# 2_MCU.net
KiCad netlist of a schematic drawn in Altium Designer
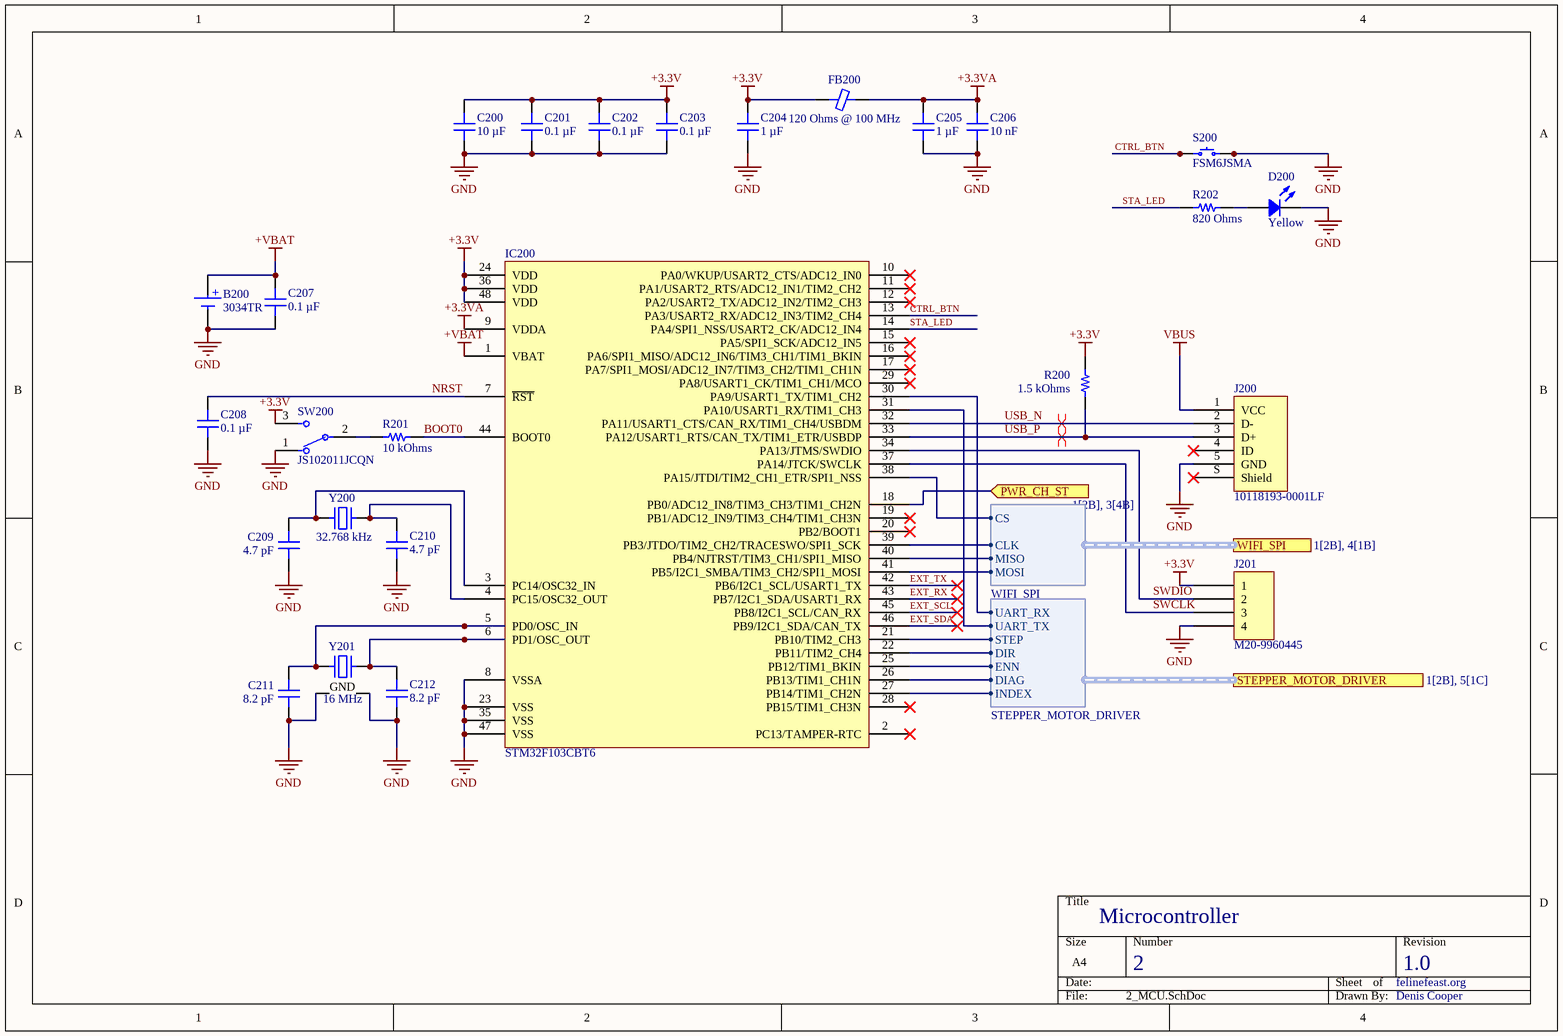
[diagram p0: 2_MCU.SchDoc]

(export (version "E")
  (design (tool "Eeschema 10.0.6"))
  (components
    (comp (ref "B200")
      (value "3034TR")
      (footprint "KEYSTONE 3034TR")
      (description "BATTERY RETAINER COIN 20MM SMD")
      (fields (field (name "MANUFACTURER") "Keystone Electronics"))
      (libsource (lib "Celestial Altium Library - altium_library") (part "KEYSTONE 3034TR"))
    )
    (comp (ref "C200")
      (value "10 µF")
      (footprint "CAP 0805_2012")
      (description "CAP CER 10UF 10V X7R 0805")
      (fields
        (field (name "PART NUMBER") "CL21B106KPQNNNE")
        (field (name "CAPACITANCE") "10 µF")
        (field (name "MANUFACTURER") "Samsung Electro-Mechanics")
      )
      (libsource (lib "Celestial Altium Library - altium_library") (part "Capacitor"))
    )
    (comp (ref "C201")
      (value "0.1 µF")
      (footprint "CAP 0603_1608")
      (description "CAP CER 0.1UF 25V X7R 0603")
      (fields
        (field (name "PART NUMBER") "CL10B104KA8NNNC")
        (field (name "CAPACITANCE") "0.1 µF")
        (field (name "MANUFACTURER") "Samsung Electro-Mechanics")
      )
      (libsource (lib "Celestial Altium Library - altium_library") (part "Capacitor"))
    )
    (comp (ref "C202")
      (value "0.1 µF")
      (footprint "CAP 0603_1608")
      (description "CAP CER 0.1UF 25V X7R 0603")
      (fields
        (field (name "PART NUMBER") "CL10B104KA8NNNC")
        (field (name "CAPACITANCE") "0.1 µF")
        (field (name "MANUFACTURER") "Samsung Electro-Mechanics")
      )
      (libsource (lib "Celestial Altium Library - altium_library") (part "Capacitor"))
    )
    (comp (ref "C203")
      (value "0.1 µF")
      (footprint "CAP 0603_1608")
      (description "CAP CER 0.1UF 25V X7R 0603")
      (fields
        (field (name "PART NUMBER") "CL10B104KA8NNNC")
        (field (name "CAPACITANCE") "0.1 µF")
        (field (name "MANUFACTURER") "Samsung Electro-Mechanics")
      )
      (libsource (lib "Celestial Altium Library - altium_library") (part "Capacitor"))
    )
    (comp (ref "C204")
      (value "1 µF")
      (footprint "CAP 0805_2012")
      (description "CAP CER 1UF 25V X7R 0805")
      (fields
        (field (name "PART NUMBER") "CL21B105KAFNFNE")
        (field (name "CAPACITANCE") "1 µF")
        (field (name "MANUFACTURER") "Samsung Electro-Mechanics")
      )
      (libsource (lib "Celestial Altium Library - altium_library") (part "Capacitor"))
    )
    (comp (ref "C205")
      (value "1 µF")
      (footprint "CAP 0805_2012")
      (description "CAP CER 1UF 25V X7R 0805")
      (fields
        (field (name "PART NUMBER") "CL21B105KAFNFNE")
        (field (name "CAPACITANCE") "1 µF")
        (field (name "MANUFACTURER") "Samsung Electro-Mechanics")
      )
      (libsource (lib "Celestial Altium Library - altium_library") (part "Capacitor"))
    )
    (comp (ref "C206")
      (value "10000 pF")
      (footprint "CAP 0603_1608")
      (description "CAP CER 10000PF 50V X7R 0603")
      (fields
        (field (name "PART NUMBER") "CL10B103KB8NNNC")
        (field (name "CAPACITANCE") "10 nF")
        (field (name "MANUFACTURER") "Samsung Electro-Mechanics")
      )
      (libsource (lib "Celestial Altium Library - altium_library") (part "Capacitor"))
    )
    (comp (ref "C207")
      (value "0.1 µF")
      (footprint "CAP 0603_1608")
      (description "CAP CER 0.1UF 25V X7R 0603")
      (fields
        (field (name "PART NUMBER") "CL10B104KA8NNNC")
        (field (name "CAPACITANCE") "0.1 µF")
        (field (name "MANUFACTURER") "Samsung Electro-Mechanics")
      )
      (libsource (lib "Celestial Altium Library - altium_library") (part "Capacitor"))
    )
    (comp (ref "C208")
      (value "0.1 µF")
      (footprint "CAP 0603_1608")
      (description "CAP CER 0.1UF 25V X7R 0603")
      (fields
        (field (name "PART NUMBER") "CL10B104KA8NNNC")
        (field (name "CAPACITANCE") "0.1 µF")
        (field (name "MANUFACTURER") "Samsung Electro-Mechanics")
      )
      (libsource (lib "Celestial Altium Library - altium_library") (part "Capacitor"))
    )
    (comp (ref "C209")
      (value "4.7 pF")
      (footprint "MURATA GJM155 0402_1005")
      (description "CAP CER 4.7PF 50V C0G/NP0 0402")
      (fields
        (field (name "PART NUMBER") "GJM1555C1H4R7GB01D")
        (field (name "CAPACITANCE") "4.7 pF")
        (field (name "MANUFACTURER") "Murata Electronics")
      )
      (libsource (lib "Celestial Altium Library - altium_library") (part "Capacitor"))
    )
    (comp (ref "C210")
      (value "4.7 pF")
      (footprint "MURATA GJM155 0402_1005")
      (description "CAP CER 4.7PF 50V C0G/NP0 0402")
      (fields
        (field (name "PART NUMBER") "GJM1555C1H4R7GB01D")
        (field (name "CAPACITANCE") "4.7 pF")
        (field (name "MANUFACTURER") "Murata Electronics")
      )
      (libsource (lib "Celestial Altium Library - altium_library") (part "Capacitor"))
    )
    (comp (ref "C211")
      (value "8.2 pF")
      (footprint "CAP 0603_1608")
      (description "CAP CER 8.2PF 50V C0G/NPO 0603")
      (fields
        (field (name "PART NUMBER") "CC0603JRNPO9BN8R2")
        (field (name "CAPACITANCE") "8.2 pF")
        (field (name "MANUFACTURER") "Yageo")
      )
      (libsource (lib "Celestial Altium Library - altium_library") (part "Capacitor"))
    )
    (comp (ref "C212")
      (value "8.2 pF")
      (footprint "CAP 0603_1608")
      (description "CAP CER 8.2PF 50V C0G/NPO 0603")
      (fields
        (field (name "PART NUMBER") "CC0603JRNPO9BN8R2")
        (field (name "CAPACITANCE") "8.2 pF")
        (field (name "MANUFACTURER") "Yageo")
      )
      (libsource (lib "Celestial Altium Library - altium_library") (part "Capacitor"))
    )
    (comp (ref "D200")
      (value "Yellow")
      (footprint "LED 0603_1608 YELLOW")
      (description "LED YELLOW DIFFUSED 0603 SMD")
      (fields
        (field (name "PART NUMBER") "LY L29K-H1K2-26-Z")
        (field (name "MANUFACTURER") "OSRAM Opto Semiconductors Inc.")
      )
      (libsource (lib "Celestial Altium Library - altium_library") (part "LED"))
    )
    (comp (ref "FB200")
      (value "120 Ohms @ 100 MHz")
      (footprint "FER 0603_1608")
      (description "FERRITE BEAD 120 OHM 0603 1LN")
      (fields
        (field (name "PART NUMBER") "GZ1608D121TF")
        (field (name "MANUFACTURER") "Shenzhen Sunlord Electronics Co., Ltd.")
      )
      (libsource (lib "Celestial Altium Library - altium_library") (part "Ferrite Chip"))
    )
    (comp (ref "IC200")
      (value "STM32F103CBT6")
      (footprint "ST LQFP-48 7X7MM")
      (description "IC MCU 32BIT 128KB FLASH 48LQFP")
      (fields (field (name "MANUFACTURER") "STMicroelectronics"))
      (libsource (lib "Celestial Altium Library - altium_library") (part "ST STM32F103 48PIN"))
    )
    (comp (ref "J200")
      (value "10118193-0001LF")
      (footprint "FCI USB 10118193-0001LF")
      (description "CONN RCPT USB2.0 MICRO B SMD R/A")
      (fields (field (name "MANUFACTURER") "Amphenol ICC (FCI)"))
      (libsource (lib "Celestial Altium Library - altium_library") (part "USB 2.0 Type B Micro"))
    )
    (comp (ref "J201")
      (value "M20-9960445")
      (footprint "HARWIN M20-9960445")
      (description "CONN HEADER R/A 4POS 2.54MM")
      (fields (field (name "MANUFACTURER") "Harwin Inc."))
      (libsource (lib "Celestial Altium Library - altium_library") (part "4 Pin"))
    )
    (comp (ref "R200")
      (value "1.5 kOhms")
      (footprint "RES 0603_1608")
      (description "RES SMD 1.5K OHM 5% 1/10W 0603")
      (fields
        (field (name "PART NUMBER") "ERJ-3GEYJ152V")
        (field (name "MANUFACTURER") "Panasonic Electronic Components")
      )
      (libsource (lib "Celestial Altium Library - altium_library") (part "Resistor"))
    )
    (comp (ref "R201")
      (value "10 kOhms")
      (footprint "RES 0603_1608")
      (description "RES SMD 10 KOHM 1% 1/5W 0603")
      (fields
        (field (name "PART NUMBER") "ERJ-P03F1002V")
        (field (name "MANUFACTURER") "Panasonic Electronic Components")
      )
      (libsource (lib "Celestial Altium Library - altium_library") (part "Resistor"))
    )
    (comp (ref "R202")
      (value "820 Ohms")
      (footprint "RES 0603_1608")
      (description "RES SMD 820 OHM 1% 1/10W 0603")
      (fields
        (field (name "PART NUMBER") "ERJ-3EKF8200V")
        (field (name "MANUFACTURER") "Panasonic Electronic Components")
      )
      (libsource (lib "Celestial Altium Library - altium_library") (part "Resistor"))
    )
    (comp (ref "S200")
      (value "FSM6JSMA")
      (footprint "TE FSM6JSMA")
      (description "SWITCH TACTILE SPST-NO 0.05A 24V")
      (fields (field (name "MANUFACTURER") "TE Connectivity ALCOSWITCH Switches"))
      (libsource (lib "Celestial Altium Library - altium_library") (part "SPST-NO 4 PIN"))
    )
    (comp (ref "SW200")
      (value "JS102011JCQN")
      (footprint "FP-JS102011JCQN-MFG")
      (description "SWITCH SLIDE SPDT 300MA 6V")
      (libsource (lib "Altium Content Vault") (part "52c419afdc2a387c7d548259a9aeefb"))
    )
    (comp (ref "Y200")
      (value "32.768 kHz")
      (footprint "ABRACON ABS07")
      (description "CRYSTAL 32.7680KHZ 7PF SMD")
      (fields
        (field (name "PART NUMBER") "ABS07-166-32.768KHZ-T")
        (field (name "MANUFACTURER") "Abracon LLC")
      )
      (libsource (lib "Celestial Altium Library - altium_library") (part "Abracon Crystal ABS07"))
    )
    (comp (ref "Y201")
      (value "16 MHz")
      (footprint "NDK NX3225GA")
      (description "CRYSTAL 16.0000MHZ 8PF SMD")
      (fields
        (field (name "PART NUMBER") "NX3225GA-16.000M-STD-CRG-2")
        (field (name "MANUFACTURER") "NDK America, Inc.")
      )
      (libsource (lib "Celestial Altium Library - altium_library") (part "NDK Crystal NX3225GA"))
    )
  )
  (nets
    (net (code "3") (name "+3.3V") (class "Default")
      (node (ref "C200") (pin "1") (pinfunction "1_1") (pintype "passive"))
      (node (ref "C201") (pin "2") (pinfunction "2_2") (pintype "passive"))
      (node (ref "C202") (pin "2") (pinfunction "2_2") (pintype "passive"))
      (node (ref "C203") (pin "2") (pinfunction "2_2") (pintype "passive"))
      (node (ref "C204") (pin "2") (pinfunction "2_2") (pintype "passive"))
      (node (ref "FB200") (pin "1") (pinfunction "1_1") (pintype "passive"))
      (node (ref "IC200") (pin "24") (pinfunction "VDD_24") (pintype "passive"))
      (node (ref "IC200") (pin "36") (pinfunction "VDD_36") (pintype "passive"))
      (node (ref "IC200") (pin "48") (pinfunction "VDD_48") (pintype "passive"))
      (node (ref "J201") (pin "1") (pinfunction "1_1") (pintype "passive"))
      (node (ref "R200") (pin "2") (pinfunction "2_2") (pintype "passive"))
      (node (ref "SW200") (pin "3") (pinfunction "3_3") (pintype "passive"))
    )
    (net (code "4") (name "+3.3VA") (class "Default")
      (node (ref "C205") (pin "2") (pinfunction "2_2") (pintype "passive"))
      (node (ref "C206") (pin "2") (pinfunction "2_2") (pintype "passive"))
      (node (ref "FB200") (pin "2") (pinfunction "2_2") (pintype "passive"))
      (node (ref "IC200") (pin "9") (pinfunction "VDDA_9") (pintype "passive"))
    )
    (net (code "5") (name "+VBAT") (class "Default")
      (node (ref "B200") (pin "1") (pinfunction "+_1") (pintype "passive"))
      (node (ref "C207") (pin "2") (pinfunction "2_2") (pintype "passive"))
      (node (ref "IC200") (pin "1") (pinfunction "VBAT_1") (pintype "passive"))
    )
    (net (code "6") (name "/BOOT0") (class "Default")
      (node (ref "IC200") (pin "44") (pinfunction "BOOT0_44") (pintype "passive"))
      (node (ref "R201") (pin "2") (pinfunction "2_2") (pintype "passive"))
    )
    (net (code "7") (name "/CLK") (class "Default")
      (node (ref "IC200") (pin "39") (pinfunction "PB3/JTDO/TIM2_CH2/TRACESWO/SPI1_SCK_39") (pintype "passive"))
    )
    (net (code "8") (name "/CS") (class "Default")
      (node (ref "IC200") (pin "38") (pinfunction "PA15/JTDI/TIM2_CH1_ETR/SPI1_NSS_38") (pintype "passive"))
    )
    (net (code "9") (name "/CTRL_BTN") (class "Default")
      (node (ref "IC200") (pin "13") (pinfunction "PA3/USART2_RX/ADC12_IN3/TIM2_CH4_13") (pintype "passive"))
      (node (ref "S200") (pin "1") (pinfunction "1_1") (pintype "passive"))
      (node (ref "S200") (pin "2") (pinfunction "2_2") (pintype "passive"))
    )
    (net (code "10") (name "/DIAG") (class "Default")
      (node (ref "IC200") (pin "26") (pinfunction "PB13/TIM1_CH1N_26") (pintype "passive"))
    )
    (net (code "11") (name "/DIR") (class "Default")
      (node (ref "IC200") (pin "22") (pinfunction "PB11/TIM2_CH4_22") (pintype "passive"))
    )
    (net (code "12") (name "/ENN") (class "Default")
      (node (ref "IC200") (pin "25") (pinfunction "PB12/TIM1_BKIN_25") (pintype "passive"))
    )
    (net (code "13") (name "/EXT_RX") (class "Default")
      (node (ref "IC200") (pin "43") (pinfunction "PB7/I2C1_SDA/USART1_RX_43") (pintype "passive+no_connect"))
    )
    (net (code "14") (name "/EXT_SCL") (class "Default")
      (node (ref "IC200") (pin "45") (pinfunction "PB8/I2C1_SCL/CAN_RX_45") (pintype "passive+no_connect"))
    )
    (net (code "15") (name "/EXT_SDA") (class "Default")
      (node (ref "IC200") (pin "46") (pinfunction "PB9/I2C1_SDA/CAN_TX_46") (pintype "passive+no_connect"))
    )
    (net (code "16") (name "/EXT_TX") (class "Default")
      (node (ref "IC200") (pin "42") (pinfunction "PB6/I2C1_SCL/USART1_TX_42") (pintype "passive+no_connect"))
    )
    (net (code "17") (name "/INDEX") (class "Default")
      (node (ref "IC200") (pin "27") (pinfunction "PB14/TIM1_CH2N_27") (pintype "passive"))
    )
    (net (code "18") (name "/MISO") (class "Default")
      (node (ref "IC200") (pin "40") (pinfunction "PB4/NJTRST/TIM3_CH1/SPI1_MISO_40") (pintype "passive"))
    )
    (net (code "19") (name "/MOSI") (class "Default")
      (node (ref "IC200") (pin "41") (pinfunction "PB5/I2C1_SMBA/TIM3_CH2/SPI1_MOSI_41") (pintype "passive"))
    )
    (net (code "20") (name "/NRST") (class "Default")
      (node (ref "C208") (pin "1") (pinfunction "1_1") (pintype "passive"))
      (node (ref "IC200") (pin "7") (pinfunction "~{RST}_7") (pintype "passive"))
    )
    (net (code "21") (name "/PWR_CH_ST") (class "Default")
      (node (ref "IC200") (pin "18") (pinfunction "PB0/ADC12_IN8/TIM3_CH3/TIM1_CH2N_18") (pintype "passive"))
    )
    (net (code "22") (name "/STA_LED") (class "Default")
      (node (ref "IC200") (pin "14") (pinfunction "PA4/SPI1_NSS/USART2_CK/ADC12_IN4_14") (pintype "passive"))
      (node (ref "R202") (pin "2") (pinfunction "2_2") (pintype "passive"))
    )
    (net (code "23") (name "/STEP") (class "Default")
      (node (ref "IC200") (pin "21") (pinfunction "PB10/TIM2_CH3_21") (pintype "passive"))
    )
    (net (code "24") (name "/SWCLK") (class "Default")
      (node (ref "IC200") (pin "37") (pinfunction "PA14/JTCK/SWCLK_37") (pintype "passive"))
      (node (ref "J201") (pin "3") (pinfunction "3_3") (pintype "passive"))
    )
    (net (code "25") (name "/SWDIO") (class "Default")
      (node (ref "IC200") (pin "34") (pinfunction "PA13/JTMS/SWDIO_34") (pintype "passive"))
      (node (ref "J201") (pin "2") (pinfunction "2_2") (pintype "passive"))
    )
    (net (code "26") (name "/UART_RX") (class "Default")
      (node (ref "IC200") (pin "30") (pinfunction "PA9/USART1_TX/TIM1_CH2_30") (pintype "passive"))
    )
    (net (code "27") (name "/UART_TX") (class "Default")
      (node (ref "IC200") (pin "31") (pinfunction "PA10/USART1_RX/TIM1_CH3_31") (pintype "passive"))
    )
    (net (code "28") (name "/USB_N") (class "Default")
      (node (ref "IC200") (pin "32") (pinfunction "PA11/USART1_CTS/CAN_RX/TIM1_CH4/USBDM_32") (pintype "passive"))
      (node (ref "J200") (pin "2") (pinfunction "D-_2") (pintype "passive"))
    )
    (net (code "29") (name "/USB_P") (class "Default")
      (node (ref "IC200") (pin "33") (pinfunction "PA12/USART1_RTS/CAN_TX/TIM1_ETR/USBDP_33") (pintype "passive"))
      (node (ref "J200") (pin "3") (pinfunction "D+_3") (pintype "passive"))
      (node (ref "R200") (pin "1") (pinfunction "1_1") (pintype "passive"))
    )
    (net (code "32") (name "GND") (class "Default")
      (node (ref "B200") (pin "2") (pinfunction "-_2") (pintype "passive"))
      (node (ref "C200") (pin "2") (pinfunction "2_2") (pintype "passive"))
      (node (ref "C201") (pin "1") (pinfunction "1_1") (pintype "passive"))
      (node (ref "C202") (pin "1") (pinfunction "1_1") (pintype "passive"))
      (node (ref "C203") (pin "1") (pinfunction "1_1") (pintype "passive"))
      (node (ref "C204") (pin "1") (pinfunction "1_1") (pintype "passive"))
      (node (ref "C205") (pin "1") (pinfunction "1_1") (pintype "passive"))
      (node (ref "C206") (pin "1") (pinfunction "1_1") (pintype "passive"))
      (node (ref "C207") (pin "1") (pinfunction "1_1") (pintype "passive"))
      (node (ref "C208") (pin "2") (pinfunction "2_2") (pintype "passive"))
      (node (ref "C209") (pin "1") (pinfunction "1_1") (pintype "passive"))
      (node (ref "C210") (pin "1") (pinfunction "1_1") (pintype "passive"))
      (node (ref "C211") (pin "2") (pinfunction "2_2") (pintype "passive"))
      (node (ref "C212") (pin "2") (pinfunction "2_2") (pintype "passive"))
      (node (ref "D200") (pin "2") (pinfunction "2_2") (pintype "passive"))
      (node (ref "IC200") (pin "23") (pinfunction "VSS_23") (pintype "passive"))
      (node (ref "IC200") (pin "35") (pinfunction "VSS_35") (pintype "passive"))
      (node (ref "IC200") (pin "47") (pinfunction "VSS_47") (pintype "passive"))
      (node (ref "IC200") (pin "8") (pinfunction "VSSA_8") (pintype "passive"))
      (node (ref "J200") (pin "5") (pinfunction "GND_5") (pintype "passive"))
      (node (ref "J201") (pin "4") (pinfunction "4_4") (pintype "passive"))
      (node (ref "S200") (pin "3") (pinfunction "3_3") (pintype "passive"))
      (node (ref "S200") (pin "4") (pinfunction "4_4") (pintype "passive"))
      (node (ref "SW200") (pin "1") (pinfunction "1_1") (pintype "passive"))
      (node (ref "Y201") (pin "2") (pinfunction "GND_2") (pintype "passive"))
      (node (ref "Y201") (pin "4") (pinfunction "GND_4") (pintype "passive"))
    )
    (net (code "33") (name "Net-(D200-Pad1)") (class "Default")
      (node (ref "D200") (pin "1") (pinfunction "1_1") (pintype "passive"))
      (node (ref "R202") (pin "1") (pinfunction "1_1") (pintype "passive"))
    )
    (net (code "34") (name "Net-(IC200-PC14{slash}OSC32_IN)") (class "Default")
      (node (ref "C209") (pin "2") (pinfunction "2_2") (pintype "passive"))
      (node (ref "IC200") (pin "3") (pinfunction "PC14/OSC32_IN_3") (pintype "passive"))
      (node (ref "Y200") (pin "1") (pinfunction "1_1") (pintype "passive"))
    )
    (net (code "35") (name "Net-(IC200-PC15{slash}OSC32_OUT)") (class "Default")
      (node (ref "C210") (pin "2") (pinfunction "2_2") (pintype "passive"))
      (node (ref "IC200") (pin "4") (pinfunction "PC15/OSC32_OUT_4") (pintype "passive"))
      (node (ref "Y200") (pin "2") (pinfunction "2_2") (pintype "passive"))
    )
    (net (code "36") (name "Net-(IC200-PD0{slash}OSC_IN)") (class "Default")
      (node (ref "C211") (pin "1") (pinfunction "1_1") (pintype "passive"))
      (node (ref "IC200") (pin "5") (pinfunction "PD0/OSC_IN_5") (pintype "passive"))
      (node (ref "Y201") (pin "1") (pinfunction "1_1") (pintype "passive"))
    )
    (net (code "37") (name "Net-(IC200-PD1{slash}OSC_OUT)") (class "Default")
      (node (ref "C212") (pin "1") (pinfunction "1_1") (pintype "passive"))
      (node (ref "IC200") (pin "6") (pinfunction "PD1/OSC_OUT_6") (pintype "passive"))
      (node (ref "Y201") (pin "3") (pinfunction "3_3") (pintype "passive"))
    )
    (net (code "38") (name "Net-(R201-Pad1)") (class "Default")
      (node (ref "R201") (pin "1") (pinfunction "1_1") (pintype "passive"))
      (node (ref "SW200") (pin "2") (pinfunction "2_2") (pintype "passive"))
    )
    (net (code "39") (name "VBUS") (class "Default")
      (node (ref "J200") (pin "1") (pinfunction "VCC_1") (pintype "passive"))
    )
    (net (code "40") (name "unconnected-(IC200-PA0{slash}WKUP{slash}USART2_CTS{slash}ADC12_IN0-Pad10)") (class "Default")
      (node (ref "IC200") (pin "10") (pinfunction "PA0/WKUP/USART2_CTS/ADC12_IN0_10") (pintype "passive+no_connect"))
    )
    (net (code "41") (name "unconnected-(IC200-PA1{slash}USART2_RTS{slash}ADC12_IN1{slash}TIM2_CH2-Pad11)") (class "Default")
      (node (ref "IC200") (pin "11") (pinfunction "PA1/USART2_RTS/ADC12_IN1/TIM2_CH2_11") (pintype "passive+no_connect"))
    )
    (net (code "42") (name "unconnected-(IC200-PA2{slash}USART2_TX{slash}ADC12_IN2{slash}TIM2_CH3-Pad12)") (class "Default")
      (node (ref "IC200") (pin "12") (pinfunction "PA2/USART2_TX/ADC12_IN2/TIM2_CH3_12") (pintype "passive+no_connect"))
    )
    (net (code "43") (name "unconnected-(IC200-PA5{slash}SPI1_SCK{slash}ADC12_IN5-Pad15)") (class "Default")
      (node (ref "IC200") (pin "15") (pinfunction "PA5/SPI1_SCK/ADC12_IN5_15") (pintype "passive+no_connect"))
    )
    (net (code "44") (name "unconnected-(IC200-PA6{slash}SPI1_MISO{slash}ADC12_IN6{slash}TIM3_CH1{slash}TIM1_BKIN-Pad16)") (class "Default")
      (node (ref "IC200") (pin "16") (pinfunction "PA6/SPI1_MISO/ADC12_IN6/TIM3_CH1/TIM1_BKIN_16") (pintype "passive+no_connect"))
    )
    (net (code "45") (name "unconnected-(IC200-PA7{slash}SPI1_MOSI{slash}ADC12_IN7{slash}TIM3_CH2{slash}TIM1_CH1N-Pad17)") (class "Default")
      (node (ref "IC200") (pin "17") (pinfunction "PA7/SPI1_MOSI/ADC12_IN7/TIM3_CH2/TIM1_CH1N_17") (pintype "passive+no_connect"))
    )
    (net (code "46") (name "unconnected-(IC200-PA8{slash}USART1_CK{slash}TIM1_CH1{slash}MCO-Pad29)") (class "Default")
      (node (ref "IC200") (pin "29") (pinfunction "PA8/USART1_CK/TIM1_CH1/MCO_29") (pintype "passive+no_connect"))
    )
    (net (code "47") (name "unconnected-(IC200-PB1{slash}ADC12_IN9{slash}TIM3_CH4{slash}TIM1_CH3N-Pad19)") (class "Default")
      (node (ref "IC200") (pin "19") (pinfunction "PB1/ADC12_IN9/TIM3_CH4/TIM1_CH3N_19") (pintype "passive+no_connect"))
    )
    (net (code "48") (name "unconnected-(IC200-PB2{slash}BOOT1-Pad20)") (class "Default")
      (node (ref "IC200") (pin "20") (pinfunction "PB2/BOOT1_20") (pintype "passive+no_connect"))
    )
    (net (code "49") (name "unconnected-(IC200-PB15{slash}TIM1_CH3N-Pad28)") (class "Default")
      (node (ref "IC200") (pin "28") (pinfunction "PB15/TIM1_CH3N_28") (pintype "passive+no_connect"))
    )
    (net (code "50") (name "unconnected-(IC200-PC13{slash}TAMPER-RTC-Pad2)") (class "Default")
      (node (ref "IC200") (pin "2") (pinfunction "PC13/TAMPER-RTC_2") (pintype "passive+no_connect"))
    )
    (net (code "51") (name "unconnected-(J200-ID-Pad4)") (class "Default")
      (node (ref "J200") (pin "4") (pinfunction "ID_4") (pintype "passive+no_connect"))
    )
    (net (code "52") (name "unconnected-(J200-Shield-PadS)") (class "Default")
      (node (ref "J200") (pin "S") (pinfunction "Shield_S") (pintype "passive+no_connect"))
    )
  )
)
